# Power_Distribution.net
KiCad netlist of a schematic drawn in Altium Designer
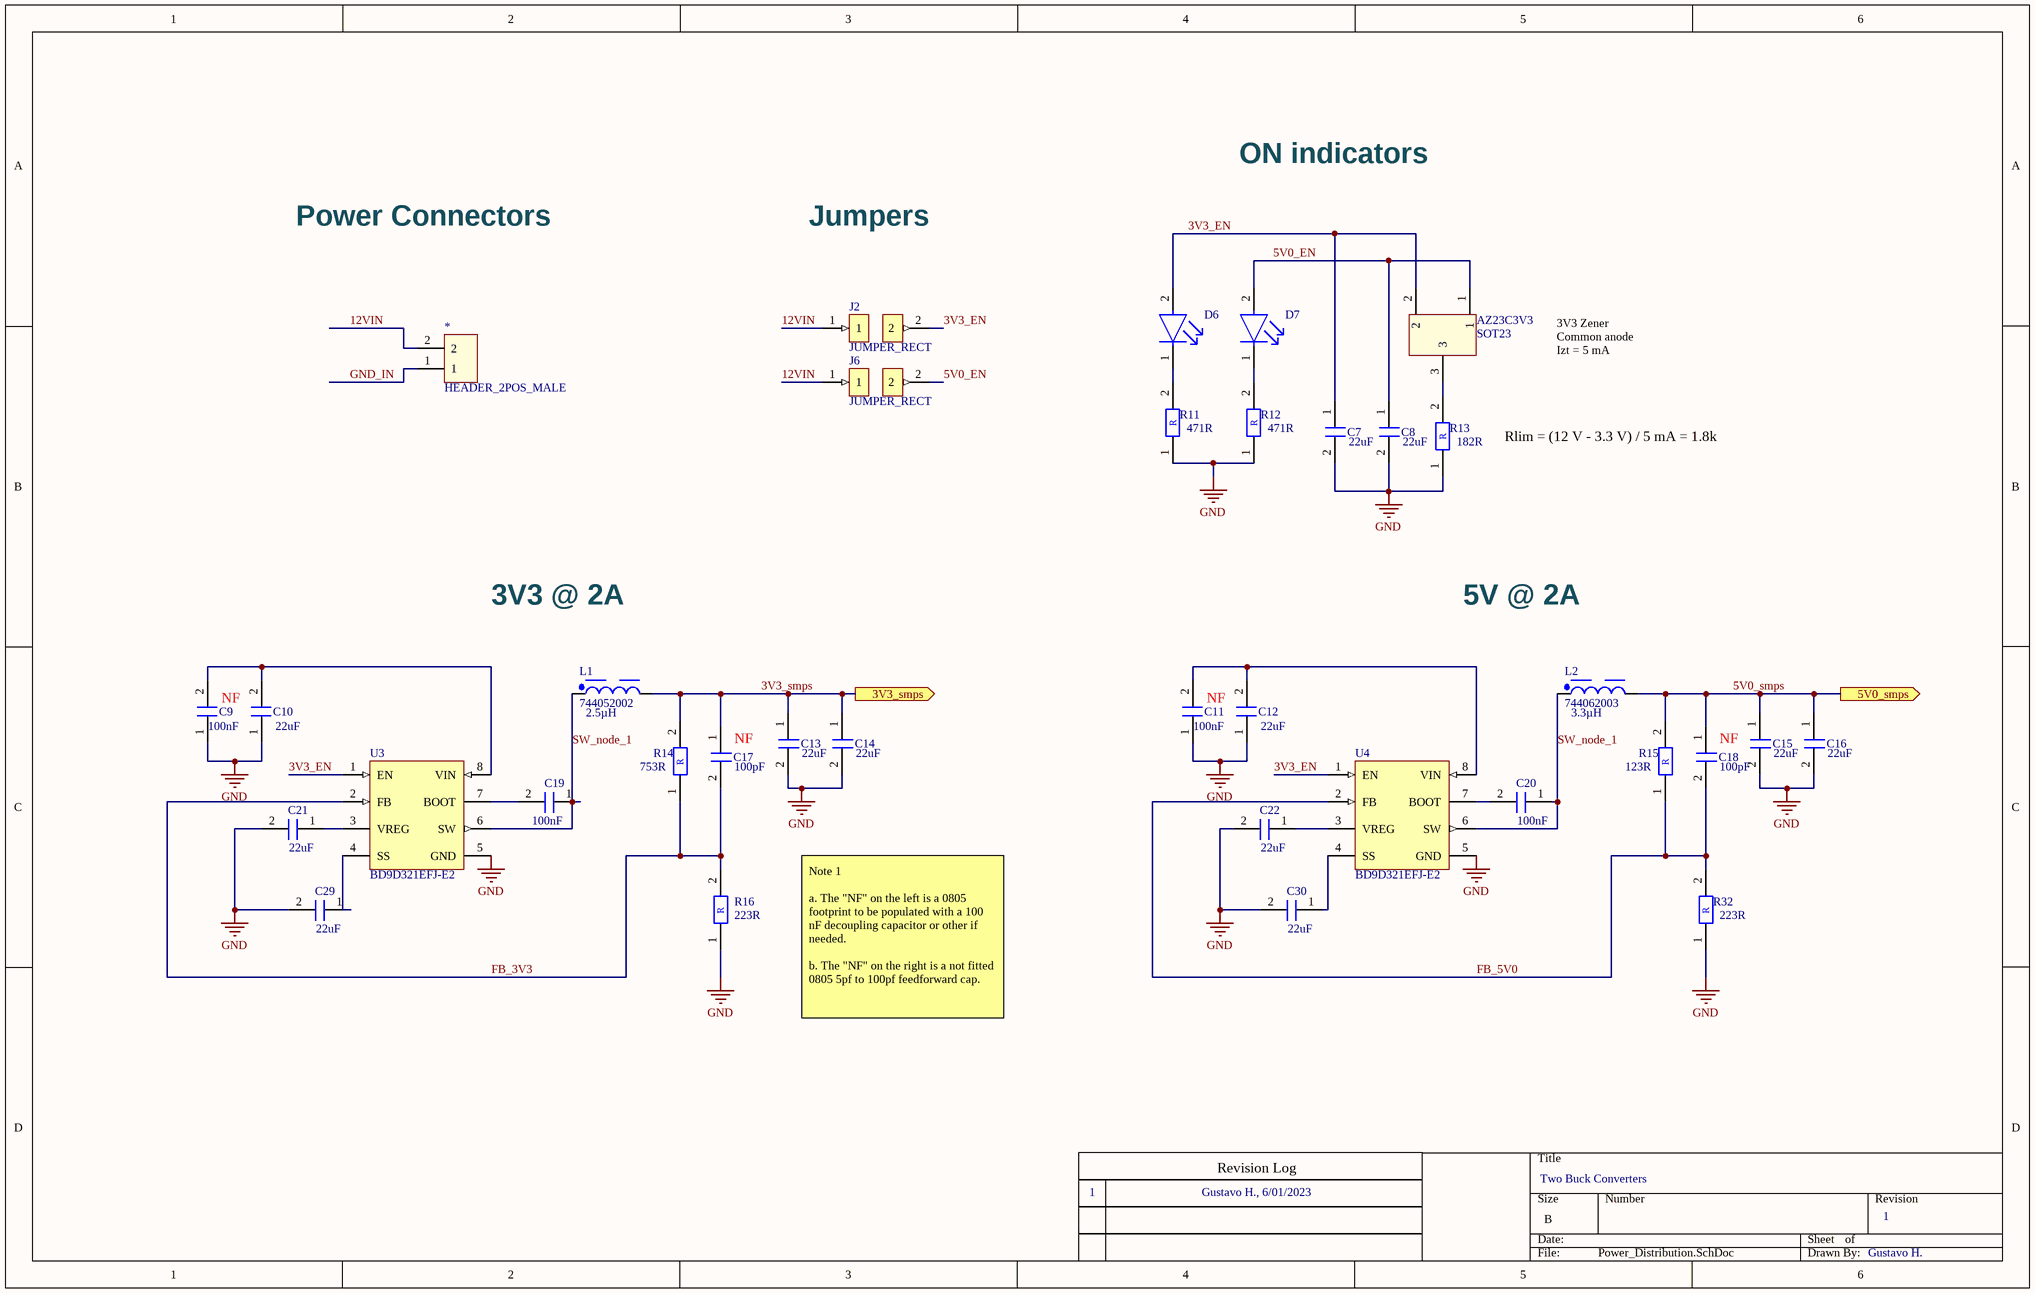
[diagram p0: Power_Distribution.SchDoc]

(export (version "E")
  (design (tool "Eeschema 10.0.6"))
  (components
    (comp (ref "*")
      (value "HEADER_2POS_MALE")
      (footprint "HEADER_2POS_MALE_VERT_2.54MM")
      (libsource (lib "CREEA_starter_library") (part "HEADER_2POS_MALE"))
    )
    (comp (ref "AZ23C3V3")
      (value "SOT23")
      (footprint "SOT23")
      (libsource (lib "CREEA_starter_library") (part "SOT23"))
    )
    (comp (ref "C7")
      (value "P.N.")
      (footprint "0805_R")
      (description "Generic 0805 Capacitor")
      (fields (field (name "CAPACITANCE") "22uF"))
      (libsource (lib "CREEA_starter_library") (part "0805_C"))
    )
    (comp (ref "C8")
      (value "P.N.")
      (footprint "0805_R")
      (description "Generic 0805 Capacitor")
      (fields (field (name "CAPACITANCE") "22uF"))
      (libsource (lib "CREEA_starter_library") (part "0805_C"))
    )
    (comp (ref "C9")
      (value "P.N.")
      (footprint "0805_R")
      (description "Generic 0805 Capacitor")
      (fields (field (name "CAPACITANCE") "100nF"))
      (libsource (lib "CREEA_starter_library") (part "0805_C"))
    )
    (comp (ref "C10")
      (value "P.N.")
      (footprint "0805_R")
      (description "Generic 0805 Capacitor")
      (fields (field (name "CAPACITANCE") "22uF"))
      (libsource (lib "CREEA_starter_library") (part "0805_C"))
    )
    (comp (ref "C11")
      (value "P.N.")
      (footprint "0805_R")
      (description "Generic 0805 Capacitor")
      (fields (field (name "CAPACITANCE") "100nF"))
      (libsource (lib "CREEA_starter_library") (part "0805_C"))
    )
    (comp (ref "C12")
      (value "P.N.")
      (footprint "0805_R")
      (description "Generic 0805 Capacitor")
      (fields (field (name "CAPACITANCE") "22uF"))
      (libsource (lib "CREEA_starter_library") (part "0805_C"))
    )
    (comp (ref "C13")
      (value "P.N.")
      (footprint "0805_R")
      (description "Generic 0805 Capacitor")
      (fields (field (name "CAPACITANCE") "22uF"))
      (libsource (lib "CREEA_starter_library") (part "0805_C"))
    )
    (comp (ref "C14")
      (value "P.N.")
      (footprint "0805_R")
      (description "Generic 0805 Capacitor")
      (fields (field (name "CAPACITANCE") "22uF"))
      (libsource (lib "CREEA_starter_library") (part "0805_C"))
    )
    (comp (ref "C15")
      (value "P.N.")
      (footprint "0805_R")
      (description "Generic 0805 Capacitor")
      (fields (field (name "CAPACITANCE") "22uF"))
      (libsource (lib "CREEA_starter_library") (part "0805_C"))
    )
    (comp (ref "C16")
      (value "P.N.")
      (footprint "0805_R")
      (description "Generic 0805 Capacitor")
      (fields (field (name "CAPACITANCE") "22uF"))
      (libsource (lib "CREEA_starter_library") (part "0805_C"))
    )
    (comp (ref "C17")
      (value "P.N.")
      (footprint "0805_R")
      (description "Generic 0805 Capacitor")
      (fields (field (name "CAPACITANCE") "100pF"))
      (libsource (lib "CREEA_starter_library") (part "0805_C"))
    )
    (comp (ref "C18")
      (value "P.N.")
      (footprint "0805_R")
      (description "Generic 0805 Capacitor")
      (fields (field (name "CAPACITANCE") "100pF"))
      (libsource (lib "CREEA_starter_library") (part "0805_C"))
    )
    (comp (ref "C19")
      (value "P.N.")
      (footprint "0805_R")
      (description "Generic 0805 Capacitor")
      (fields (field (name "CAPACITANCE") "100nF"))
      (libsource (lib "CREEA_starter_library") (part "0805_C"))
    )
    (comp (ref "C20")
      (value "P.N.")
      (footprint "0805_R")
      (description "Generic 0805 Capacitor")
      (fields (field (name "CAPACITANCE") "100nF"))
      (libsource (lib "CREEA_starter_library") (part "0805_C"))
    )
    (comp (ref "C21")
      (value "P.N.")
      (footprint "0805_R")
      (description "Generic 0805 Capacitor")
      (fields (field (name "CAPACITANCE") "22uF"))
      (libsource (lib "CREEA_starter_library") (part "0805_C"))
    )
    (comp (ref "C22")
      (value "P.N.")
      (footprint "0805_R")
      (description "Generic 0805 Capacitor")
      (fields (field (name "CAPACITANCE") "22uF"))
      (libsource (lib "CREEA_starter_library") (part "0805_C"))
    )
    (comp (ref "C29")
      (value "P.N.")
      (footprint "0805_R")
      (description "Generic 0805 Capacitor")
      (fields (field (name "CAPACITANCE") "22uF"))
      (libsource (lib "CREEA_starter_library") (part "0805_C"))
    )
    (comp (ref "C30")
      (value "P.N.")
      (footprint "0805_R")
      (description "Generic 0805 Capacitor")
      (fields (field (name "CAPACITANCE") "22uF"))
      (libsource (lib "CREEA_starter_library") (part "0805_C"))
    )
    (comp (ref "D6")
      (value "LTST-C191TBKT")
      (footprint "FP-LTST-C191TBKT-MFG")
      (description "LED BLUE CLEAR CHIP SMD")
      (libsource (lib "Altium Content Vault") (part "8706943c75ba83719d021d2fdc84c58"))
    )
    (comp (ref "D7")
      (value "LTST-C191TBKT")
      (footprint "FP-LTST-C191TBKT-MFG")
      (description "LED BLUE CLEAR CHIP SMD")
      (libsource (lib "Altium Content Vault") (part "8706943c75ba83719d021d2fdc84c58"))
    )
    (comp (ref "J2")
      (value "JUMPER_RECT")
      (description "Small rectangular jumper")
      (libsource (lib "CREEA_starter_library") (part "JUMPER_RECT"))
    )
    (comp (ref "J6")
      (value "JUMPER_RECT")
      (description "Small rectangular jumper")
      (libsource (lib "CREEA_starter_library") (part "JUMPER_RECT"))
    )
    (comp (ref "L1")
      (value "744052002")
      (footprint "WE-TPC_5818")
      (fields (field (name "INDUCTANCE") "2.5µH"))
      (libsource (lib "Altium Content Vault") (part "Inductor - 2"))
    )
    (comp (ref "L2")
      (value "744062003")
      (footprint "WE-TPC_6823")
      (fields (field (name "TOLERANCE") "30%") (field (name "INDUCTANCE") "3.3µH"))
      (libsource (lib "Altium Content Vault") (part "Inductor - 2"))
    )
    (comp (ref "R11")
      (value "P.N.")
      (footprint "0805_R")
      (description "Generic 0805 Resistor")
      (fields (field (name "RESISTANCE") "471R"))
      (libsource (lib "CREEA_starter_library") (part "0805_R"))
    )
    (comp (ref "R12")
      (value "P.N.")
      (footprint "0805_R")
      (description "Generic 0805 Resistor")
      (fields (field (name "RESISTANCE") "471R"))
      (libsource (lib "CREEA_starter_library") (part "0805_R"))
    )
    (comp (ref "R13")
      (value "P.N.")
      (footprint "0805_R")
      (description "Generic 0805 Resistor")
      (fields (field (name "RESISTANCE") "182R"))
      (libsource (lib "CREEA_starter_library") (part "0805_R"))
    )
    (comp (ref "R14")
      (value "P.N.")
      (footprint "0805_R")
      (description "Generic 0805 Resistor")
      (fields (field (name "RESISTANCE") "753R"))
      (libsource (lib "CREEA_starter_library") (part "0805_R"))
    )
    (comp (ref "R15")
      (value "P.N.")
      (footprint "0805_R")
      (description "Generic 0805 Resistor")
      (fields (field (name "RESISTANCE") "123R"))
      (libsource (lib "CREEA_starter_library") (part "0805_R"))
    )
    (comp (ref "R16")
      (value "P.N.")
      (footprint "0805_R")
      (description "Generic 0805 Resistor")
      (fields (field (name "RESISTANCE") "223R"))
      (libsource (lib "CREEA_starter_library") (part "0805_R"))
    )
    (comp (ref "R32")
      (value "P.N.")
      (footprint "0805_R")
      (description "Generic 0805 Resistor")
      (fields (field (name "RESISTANCE") "223R"))
      (libsource (lib "CREEA_starter_library") (part "0805_R"))
    )
    (comp (ref "U3")
      (value "BD9D321EFJ-E2")
      (footprint "SOIC127P600X100-8N")
      (description "ICREGBUCKADJ3ASYNC8HTSOP")
      (libsource (lib "Cetys University") (part "BD9D321EFJ-E2-Symbol-1"))
    )
    (comp (ref "U4")
      (value "BD9D321EFJ-E2")
      (footprint "SOIC127P600X100-8N")
      (description "ICREGBUCKADJ3ASYNC8HTSOP")
      (libsource (lib "Cetys University") (part "BD9D321EFJ-E2-Symbol-1"))
    )
  )
  (nets
    (net (code "1") (name "/3V3_EN") (class "Default")
      (node (ref "AZ23C3V3") (pin "2") (pinfunction "2_2") (pintype "passive"))
      (node (ref "C7") (pin "1") (pinfunction "1_1") (pintype "passive"))
      (node (ref "D6") (pin "2") (pinfunction "A_2") (pintype "passive"))
      (node (ref "J2") (pin "2") (pinfunction "2_2") (pintype "output"))
      (node (ref "U3") (pin "1") (pinfunction "EN_1") (pintype "input"))
      (node (ref "U4") (pin "1") (pinfunction "EN_1") (pintype "input"))
    )
    (net (code "2") (name "/3V3_smps") (class "Default")
      (node (ref "C13") (pin "1") (pinfunction "1_1") (pintype "passive"))
      (node (ref "C14") (pin "1") (pinfunction "1_1") (pintype "passive"))
      (node (ref "C17") (pin "1") (pinfunction "1_1") (pintype "passive"))
      (node (ref "L1") (pin "2") (pinfunction "2_2") (pintype "passive"))
      (node (ref "R14") (pin "2") (pinfunction "2_2") (pintype "passive"))
    )
    (net (code "3") (name "/5V0_EN") (class "Default")
      (node (ref "AZ23C3V3") (pin "1") (pinfunction "1_1") (pintype "passive"))
      (node (ref "C8") (pin "1") (pinfunction "1_1") (pintype "passive"))
      (node (ref "D7") (pin "2") (pinfunction "A_2") (pintype "passive"))
      (node (ref "J6") (pin "2") (pinfunction "2_2") (pintype "output"))
    )
    (net (code "4") (name "/5V0_smps") (class "Default")
      (node (ref "C15") (pin "1") (pinfunction "1_1") (pintype "passive"))
      (node (ref "C16") (pin "1") (pinfunction "1_1") (pintype "passive"))
      (node (ref "C18") (pin "1") (pinfunction "1_1") (pintype "passive"))
      (node (ref "L2") (pin "2") (pinfunction "2_2") (pintype "passive"))
      (node (ref "R15") (pin "2") (pinfunction "2_2") (pintype "passive"))
    )
    (net (code "5") (name "/12VIN") (class "Default")
      (node (ref "*") (pin "2") (pinfunction "2_2") (pintype "passive"))
      (node (ref "J2") (pin "1") (pinfunction "1_1") (pintype "input"))
      (node (ref "J6") (pin "1") (pinfunction "1_1") (pintype "input"))
    )
    (net (code "6") (name "/FB_3V3") (class "Default")
      (node (ref "C17") (pin "2") (pinfunction "2_2") (pintype "passive"))
      (node (ref "R14") (pin "1") (pinfunction "1_1") (pintype "passive"))
      (node (ref "R16") (pin "2") (pinfunction "2_2") (pintype "passive"))
      (node (ref "U3") (pin "2") (pinfunction "FB_2") (pintype "input"))
    )
    (net (code "7") (name "/FB_5V0") (class "Default")
      (node (ref "C18") (pin "2") (pinfunction "2_2") (pintype "passive"))
      (node (ref "R15") (pin "1") (pinfunction "1_1") (pintype "passive"))
      (node (ref "R32") (pin "2") (pinfunction "2_2") (pintype "passive"))
      (node (ref "U4") (pin "2") (pinfunction "FB_2") (pintype "input"))
    )
    (net (code "8") (name "/GND_IN") (class "Default")
      (node (ref "*") (pin "1") (pinfunction "1_1") (pintype "passive"))
    )
    (net (code "9") (name "/SW_node_1") (class "Default")
      (node (ref "C19") (pin "1") (pinfunction "1_1") (pintype "passive"))
      (node (ref "C20") (pin "1") (pinfunction "1_1") (pintype "passive"))
      (node (ref "L1") (pin "1") (pinfunction "1_1") (pintype "passive"))
      (node (ref "L2") (pin "1") (pinfunction "1_1") (pintype "passive"))
      (node (ref "U3") (pin "6") (pinfunction "SW_6") (pintype "output"))
      (node (ref "U4") (pin "6") (pinfunction "SW_6") (pintype "output"))
    )
    (net (code "10") (name "GND") (class "Default")
      (node (ref "C10") (pin "1") (pinfunction "1_1") (pintype "passive"))
      (node (ref "C11") (pin "1") (pinfunction "1_1") (pintype "passive"))
      (node (ref "C12") (pin "1") (pinfunction "1_1") (pintype "passive"))
      (node (ref "C13") (pin "2") (pinfunction "2_2") (pintype "passive"))
      (node (ref "C14") (pin "2") (pinfunction "2_2") (pintype "passive"))
      (node (ref "C15") (pin "2") (pinfunction "2_2") (pintype "passive"))
      (node (ref "C16") (pin "2") (pinfunction "2_2") (pintype "passive"))
      (node (ref "C21") (pin "2") (pinfunction "2_2") (pintype "passive"))
      (node (ref "C22") (pin "2") (pinfunction "2_2") (pintype "passive"))
      (node (ref "C29") (pin "2") (pinfunction "2_2") (pintype "passive"))
      (node (ref "C30") (pin "2") (pinfunction "2_2") (pintype "passive"))
      (node (ref "C7") (pin "2") (pinfunction "2_2") (pintype "passive"))
      (node (ref "C8") (pin "2") (pinfunction "2_2") (pintype "passive"))
      (node (ref "C9") (pin "1") (pinfunction "1_1") (pintype "passive"))
      (node (ref "R11") (pin "1") (pinfunction "1_1") (pintype "passive"))
      (node (ref "R12") (pin "1") (pinfunction "1_1") (pintype "passive"))
      (node (ref "R13") (pin "1") (pinfunction "1_1") (pintype "passive"))
      (node (ref "R16") (pin "1") (pinfunction "1_1") (pintype "passive"))
      (node (ref "R32") (pin "1") (pinfunction "1_1") (pintype "passive"))
      (node (ref "U3") (pin "5") (pinfunction "GND_5") (pintype "passive"))
      (node (ref "U4") (pin "5") (pinfunction "GND_5") (pintype "passive"))
    )
    (net (code "11") (name "Net-(AZ23C3V3-Pad3)") (class "Default")
      (node (ref "AZ23C3V3") (pin "3") (pinfunction "3_3") (pintype "passive"))
      (node (ref "R13") (pin "2") (pinfunction "2_2") (pintype "passive"))
    )
    (net (code "12") (name "Net-(D6-C)") (class "Default")
      (node (ref "D6") (pin "1") (pinfunction "C_1") (pintype "passive"))
      (node (ref "R11") (pin "2") (pinfunction "2_2") (pintype "passive"))
    )
    (net (code "13") (name "Net-(D7-C)") (class "Default")
      (node (ref "D7") (pin "1") (pinfunction "C_1") (pintype "passive"))
      (node (ref "R12") (pin "2") (pinfunction "2_2") (pintype "passive"))
    )
    (net (code "14") (name "Net-(U3-BOOT)") (class "Default")
      (node (ref "C19") (pin "2") (pinfunction "2_2") (pintype "passive"))
      (node (ref "U3") (pin "7") (pinfunction "BOOT_7") (pintype "passive"))
    )
    (net (code "15") (name "Net-(U3-SS)") (class "Default")
      (node (ref "C29") (pin "1") (pinfunction "1_1") (pintype "passive"))
      (node (ref "U3") (pin "4") (pinfunction "SS_4") (pintype "passive"))
    )
    (net (code "16") (name "Net-(U3-VIN)") (class "Default")
      (node (ref "C10") (pin "2") (pinfunction "2_2") (pintype "passive"))
      (node (ref "C9") (pin "2") (pinfunction "2_2") (pintype "passive"))
      (node (ref "U3") (pin "8") (pinfunction "VIN_8") (pintype "input"))
    )
    (net (code "17") (name "Net-(U3-VREG)") (class "Default")
      (node (ref "C21") (pin "1") (pinfunction "1_1") (pintype "passive"))
      (node (ref "U3") (pin "3") (pinfunction "VREG_3") (pintype "passive"))
    )
    (net (code "18") (name "Net-(U4-BOOT)") (class "Default")
      (node (ref "C20") (pin "2") (pinfunction "2_2") (pintype "passive"))
      (node (ref "U4") (pin "7") (pinfunction "BOOT_7") (pintype "passive"))
    )
    (net (code "19") (name "Net-(U4-SS)") (class "Default")
      (node (ref "C30") (pin "1") (pinfunction "1_1") (pintype "passive"))
      (node (ref "U4") (pin "4") (pinfunction "SS_4") (pintype "passive"))
    )
    (net (code "20") (name "Net-(U4-VIN)") (class "Default")
      (node (ref "C11") (pin "2") (pinfunction "2_2") (pintype "passive"))
      (node (ref "C12") (pin "2") (pinfunction "2_2") (pintype "passive"))
      (node (ref "U4") (pin "8") (pinfunction "VIN_8") (pintype "input"))
    )
    (net (code "21") (name "Net-(U4-VREG)") (class "Default")
      (node (ref "C22") (pin "1") (pinfunction "1_1") (pintype "passive"))
      (node (ref "U4") (pin "3") (pinfunction "VREG_3") (pintype "passive"))
    )
  )
)
